# LED_POWER.net
KiCad netlist of a schematic drawn in Altium Designer
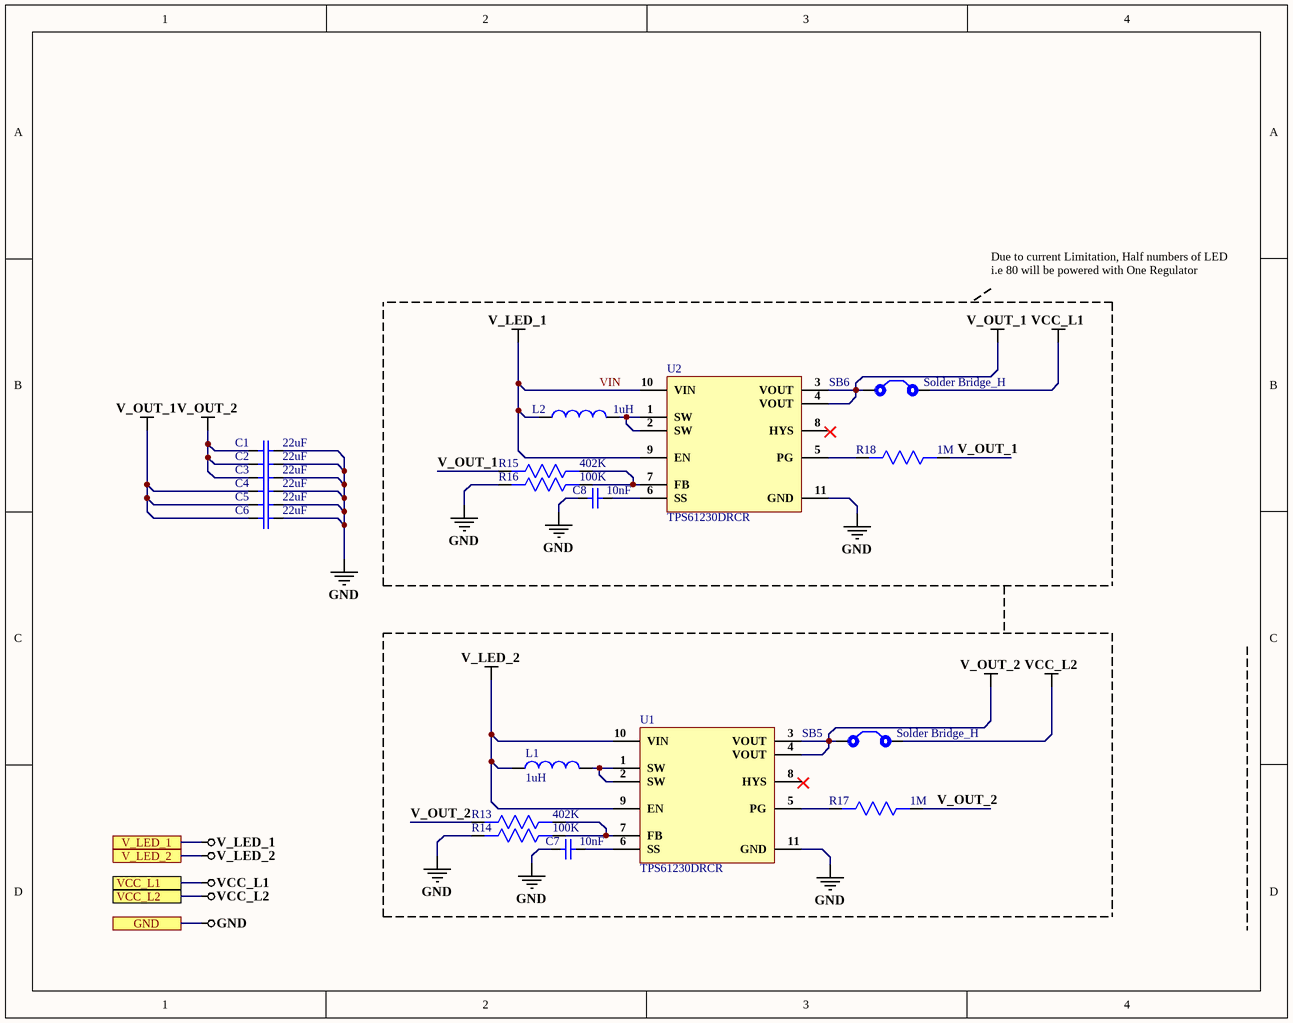
[diagram p0: LED_POWER.SchDoc]

(export (version "E")
  (design (tool "Eeschema 10.0.6"))
  (components
    (comp (ref "C1")
      (value "22uF")
      (footprint "Cap0805")
      (description "CAP CER 22UF 6.3V X5R 0805")
      (fields
        (field (name "MANUFACTURER") "Murata")
        (field (name "MANUFACTURER PART NUMBER") "GRM21BR60J226ME39K")
      )
      (libsource (lib "TT_IntLib") (part "GRM21BR60J226ME39K"))
    )
    (comp (ref "C2")
      (value "22uF")
      (footprint "Cap0805")
      (description "CAP CER 22UF 6.3V X5R 0805")
      (fields
        (field (name "MANUFACTURER") "Murata")
        (field (name "MANUFACTURER PART NUMBER") "GRM21BR60J226ME39K")
      )
      (libsource (lib "TT_IntLib") (part "GRM21BR60J226ME39K"))
    )
    (comp (ref "C3")
      (value "22uF")
      (footprint "Cap0805")
      (description "CAP CER 22UF 6.3V X5R 0805")
      (fields
        (field (name "MANUFACTURER") "Murata")
        (field (name "MANUFACTURER PART NUMBER") "GRM21BR60J226ME39K")
      )
      (libsource (lib "TT_IntLib") (part "GRM21BR60J226ME39K"))
    )
    (comp (ref "C4")
      (value "22uF")
      (footprint "Cap0805")
      (description "CAP CER 22UF 6.3V X5R 0805")
      (fields
        (field (name "MANUFACTURER") "Murata")
        (field (name "MANUFACTURER PART NUMBER") "GRM21BR60J226ME39K")
      )
      (libsource (lib "TT_IntLib") (part "GRM21BR60J226ME39K"))
    )
    (comp (ref "C5")
      (value "22uF")
      (footprint "Cap0805")
      (description "CAP CER 22UF 6.3V X5R 0805")
      (fields
        (field (name "MANUFACTURER") "Murata")
        (field (name "MANUFACTURER PART NUMBER") "GRM21BR60J226ME39K")
      )
      (libsource (lib "TT_IntLib") (part "GRM21BR60J226ME39K"))
    )
    (comp (ref "C6")
      (value "22uF")
      (footprint "Cap0805")
      (description "CAP CER 22UF 6.3V X5R 0805")
      (fields
        (field (name "MANUFACTURER") "Murata")
        (field (name "MANUFACTURER PART NUMBER") "GRM21BR60J226ME39K")
      )
      (libsource (lib "TT_IntLib") (part "GRM21BR60J226ME39K"))
    )
    (comp (ref "C7")
      (value "10nF")
      (footprint "CAP 0201")
      (description "CAP CER 10000PF 16V X7R 0201")
      (fields
        (field (name "MANUFACTURER") "Murata")
        (field (name "MANUFACTURER PART NUMBER") "GRM033R71C103KE14D")
      )
      (libsource (lib "TT_IntLib") (part "GRM033R71C103KE14D"))
    )
    (comp (ref "C8")
      (value "10nF")
      (footprint "CAP 0201")
      (description "CAP CER 10000PF 16V X7R 0201")
      (fields
        (field (name "MANUFACTURER") "Murata")
        (field (name "MANUFACTURER PART NUMBER") "GRM033R71C103KE14D")
      )
      (libsource (lib "TT_IntLib") (part "GRM033R71C103KE14D"))
    )
    (comp (ref "L1")
      (value "1uH")
      (footprint "1255AY-1R0N=P3")
      (description "FIXED IND 1UH 6.5A 10 MOHM SMD")
      (fields
        (field (name "MANUFACTURER") "Murata")
        (field (name "MANUFACTURER PART NUMBER") "1255AY-1R0N=P3")
      )
      (libsource (lib "TT_IntLib") (part "1255AY-1R0N=P3"))
    )
    (comp (ref "L2")
      (value "1uH")
      (footprint "1255AY-1R0N=P3")
      (description "FIXED IND 1UH 6.5A 10 MOHM SMD")
      (fields
        (field (name "MANUFACTURER") "Murata")
        (field (name "MANUFACTURER PART NUMBER") "1255AY-1R0N=P3")
      )
      (libsource (lib "TT_IntLib") (part "1255AY-1R0N=P3"))
    )
    (comp (ref "R13")
      (value "402K")
      (footprint "Res0603")
      (description "RES 402K OHM 1% 1/10W 0603")
      (fields
        (field (name "MANUFACTURER") "KOA Speer")
        (field (name "MANUFACTURER PART NUMBER") "RK73H1JTTD4023F")
      )
      (libsource (lib "TT_IntLib") (part "RK73H1JTTD4023F"))
    )
    (comp (ref "R14")
      (value "100K")
      (footprint "Res0402")
      (description "RES 100K OHM 1% 1/10W 0402")
      (fields
        (field (name "MANUFACTURER") "KOA Speer")
        (field (name "MANUFACTURER PART NUMBER") "RK73H1ETTP1003F")
      )
      (libsource (lib "TT_IntLib") (part "RK73H1ETTP1003F"))
    )
    (comp (ref "R15")
      (value "402K")
      (footprint "Res0603")
      (description "RES 402K OHM 1% 1/10W 0603")
      (fields
        (field (name "MANUFACTURER") "KOA Speer")
        (field (name "MANUFACTURER PART NUMBER") "RK73H1JTTD4023F")
      )
      (libsource (lib "TT_IntLib") (part "RK73H1JTTD4023F"))
    )
    (comp (ref "R16")
      (value "100K")
      (footprint "Res0402")
      (description "RES 100K OHM 1% 1/10W 0402")
      (fields
        (field (name "MANUFACTURER") "KOA Speer")
        (field (name "MANUFACTURER PART NUMBER") "RK73H1ETTP1003F")
      )
      (libsource (lib "TT_IntLib") (part "RK73H1ETTP1003F"))
    )
    (comp (ref "R17")
      (value "1M")
      (footprint "Res0402")
      (description "RES 1M OHM 1% 1/10W 0402")
      (fields
        (field (name "MANUFACTURER") "KOA Speer")
        (field (name "MANUFACTURER PART NUMBER") "RK73G1ETTP1004F")
      )
      (libsource (lib "TT_IntLib") (part "RK73G1ETTP1004F"))
    )
    (comp (ref "R18")
      (value "1M")
      (footprint "Res0402")
      (description "RES 1M OHM 1% 1/10W 0402")
      (fields
        (field (name "MANUFACTURER") "KOA Speer")
        (field (name "MANUFACTURER PART NUMBER") "RK73G1ETTP1004F")
      )
      (libsource (lib "TT_IntLib") (part "RK73G1ETTP1004F"))
    )
    (comp (ref "SB5")
      (value "Solder Bridge_H")
      (footprint "Solder Bridge throgh hole")
      (description "Solder Bridge ON")
      (libsource (lib "TT_IntLib") (part "Solder Bridge Trough hole"))
    )
    (comp (ref "SB6")
      (value "Solder Bridge_H")
      (footprint "Solder Bridge throgh hole")
      (description "Solder Bridge ON")
      (libsource (lib "TT_IntLib") (part "Solder Bridge Trough hole"))
    )
    (comp (ref "U1")
      (value "TPS61230DRCR")
      (footprint "10-VSON (3x3)")
      (description "IC REG BOOST ADJ 4A 10VSON")
      (fields (field (name "MANUFACTURER") "Texas Instruments"))
      (libsource (lib "TT_IntLib") (part "TPS61230DRCR"))
    )
    (comp (ref "U2")
      (value "TPS61230DRCR")
      (footprint "10-VSON (3x3)")
      (description "IC REG BOOST ADJ 4A 10VSON")
      (fields (field (name "MANUFACTURER") "Texas Instruments"))
      (libsource (lib "TT_IntLib") (part "TPS61230DRCR"))
    )
  )
  (nets
    (net (code "1") (name "GND") (class "Default")
      (node (ref "C1") (pin "1") (pintype "passive"))
      (node (ref "C2") (pin "1") (pintype "passive"))
      (node (ref "C3") (pin "1") (pintype "passive"))
      (node (ref "C4") (pin "1") (pintype "passive"))
      (node (ref "C5") (pin "1") (pintype "passive"))
      (node (ref "C6") (pin "1") (pintype "passive"))
      (node (ref "C7") (pin "2") (pintype "passive"))
      (node (ref "C8") (pin "2") (pintype "passive"))
      (node (ref "R14") (pin "2") (pintype "passive"))
      (node (ref "R16") (pin "2") (pintype "passive"))
      (node (ref "U1") (pin "11") (pinfunction "GND_11") (pintype "passive"))
      (node (ref "U2") (pin "11") (pinfunction "GND_11") (pintype "passive"))
    )
    (net (code "2") (name "Net-(L1-Pad1)") (class "Default")
      (node (ref "L1") (pin "1") (pinfunction "1_1") (pintype "passive"))
      (node (ref "U1") (pin "1") (pinfunction "SW_1") (pintype "passive"))
      (node (ref "U1") (pin "2") (pinfunction "SW_2") (pintype "passive"))
    )
    (net (code "3") (name "Net-(L2-Pad1)") (class "Default")
      (node (ref "L2") (pin "1") (pinfunction "1_1") (pintype "passive"))
      (node (ref "U2") (pin "1") (pinfunction "SW_1") (pintype "passive"))
      (node (ref "U2") (pin "2") (pinfunction "SW_2") (pintype "passive"))
    )
    (net (code "4") (name "Net-(U1-FB)") (class "Default")
      (node (ref "R13") (pin "1") (pintype "passive"))
      (node (ref "R14") (pin "1") (pintype "passive"))
      (node (ref "U1") (pin "7") (pinfunction "FB_7") (pintype "passive"))
    )
    (net (code "5") (name "Net-(U1-PG)") (class "Default")
      (node (ref "R17") (pin "2") (pintype "passive"))
      (node (ref "U1") (pin "5") (pinfunction "PG_5") (pintype "passive"))
    )
    (net (code "6") (name "Net-(U1-SS)") (class "Default")
      (node (ref "C7") (pin "1") (pintype "passive"))
      (node (ref "U1") (pin "6") (pinfunction "SS_6") (pintype "passive"))
    )
    (net (code "7") (name "Net-(U2-FB)") (class "Default")
      (node (ref "R15") (pin "1") (pintype "passive"))
      (node (ref "R16") (pin "1") (pintype "passive"))
      (node (ref "U2") (pin "7") (pinfunction "FB_7") (pintype "passive"))
    )
    (net (code "8") (name "Net-(U2-PG)") (class "Default")
      (node (ref "R18") (pin "2") (pintype "passive"))
      (node (ref "U2") (pin "5") (pinfunction "PG_5") (pintype "passive"))
    )
    (net (code "9") (name "Net-(U2-SS)") (class "Default")
      (node (ref "C8") (pin "1") (pintype "passive"))
      (node (ref "U2") (pin "6") (pinfunction "SS_6") (pintype "passive"))
    )
    (net (code "10") (name "VCC_L1") (class "Default")
      (node (ref "SB6") (pin "2") (pinfunction "2_2") (pintype "passive"))
    )
    (net (code "11") (name "VCC_L2") (class "Default")
      (node (ref "SB5") (pin "2") (pinfunction "2_2") (pintype "passive"))
    )
    (net (code "12") (name "V_LED_1") (class "Default")
      (node (ref "L2") (pin "2") (pinfunction "2_2") (pintype "passive"))
      (node (ref "U2") (pin "10") (pinfunction "VIN_10") (pintype "passive"))
      (node (ref "U2") (pin "9") (pinfunction "EN_9") (pintype "passive"))
    )
    (net (code "13") (name "V_LED_2") (class "Default")
      (node (ref "L1") (pin "2") (pinfunction "2_2") (pintype "passive"))
      (node (ref "U1") (pin "10") (pinfunction "VIN_10") (pintype "passive"))
      (node (ref "U1") (pin "9") (pinfunction "EN_9") (pintype "passive"))
    )
    (net (code "14") (name "V_OUT_1") (class "Default")
      (node (ref "C4") (pin "2") (pintype "passive"))
      (node (ref "C5") (pin "2") (pintype "passive"))
      (node (ref "C6") (pin "2") (pintype "passive"))
      (node (ref "R15") (pin "2") (pintype "passive"))
      (node (ref "R18") (pin "1") (pintype "passive"))
      (node (ref "SB6") (pin "1") (pinfunction "1_1") (pintype "passive"))
      (node (ref "U2") (pin "3") (pinfunction "VOUT_3") (pintype "passive"))
      (node (ref "U2") (pin "4") (pinfunction "VOUT_4") (pintype "passive"))
    )
    (net (code "15") (name "V_OUT_2") (class "Default")
      (node (ref "C1") (pin "2") (pintype "passive"))
      (node (ref "C2") (pin "2") (pintype "passive"))
      (node (ref "C3") (pin "2") (pintype "passive"))
      (node (ref "R13") (pin "2") (pintype "passive"))
      (node (ref "R17") (pin "1") (pintype "passive"))
      (node (ref "SB5") (pin "1") (pinfunction "1_1") (pintype "passive"))
      (node (ref "U1") (pin "3") (pinfunction "VOUT_3") (pintype "passive"))
      (node (ref "U1") (pin "4") (pinfunction "VOUT_4") (pintype "passive"))
    )
    (net (code "16") (name "unconnected-(U1-HYS-Pad8)") (class "Default")
      (node (ref "U1") (pin "8") (pinfunction "HYS_8") (pintype "passive"))
    )
    (net (code "17") (name "unconnected-(U2-HYS-Pad8)") (class "Default")
      (node (ref "U2") (pin "8") (pinfunction "HYS_8") (pintype "passive"))
    )
  )
)
